# STM32F103UART3.net
KiCad netlist of a schematic drawn in Altium Designer
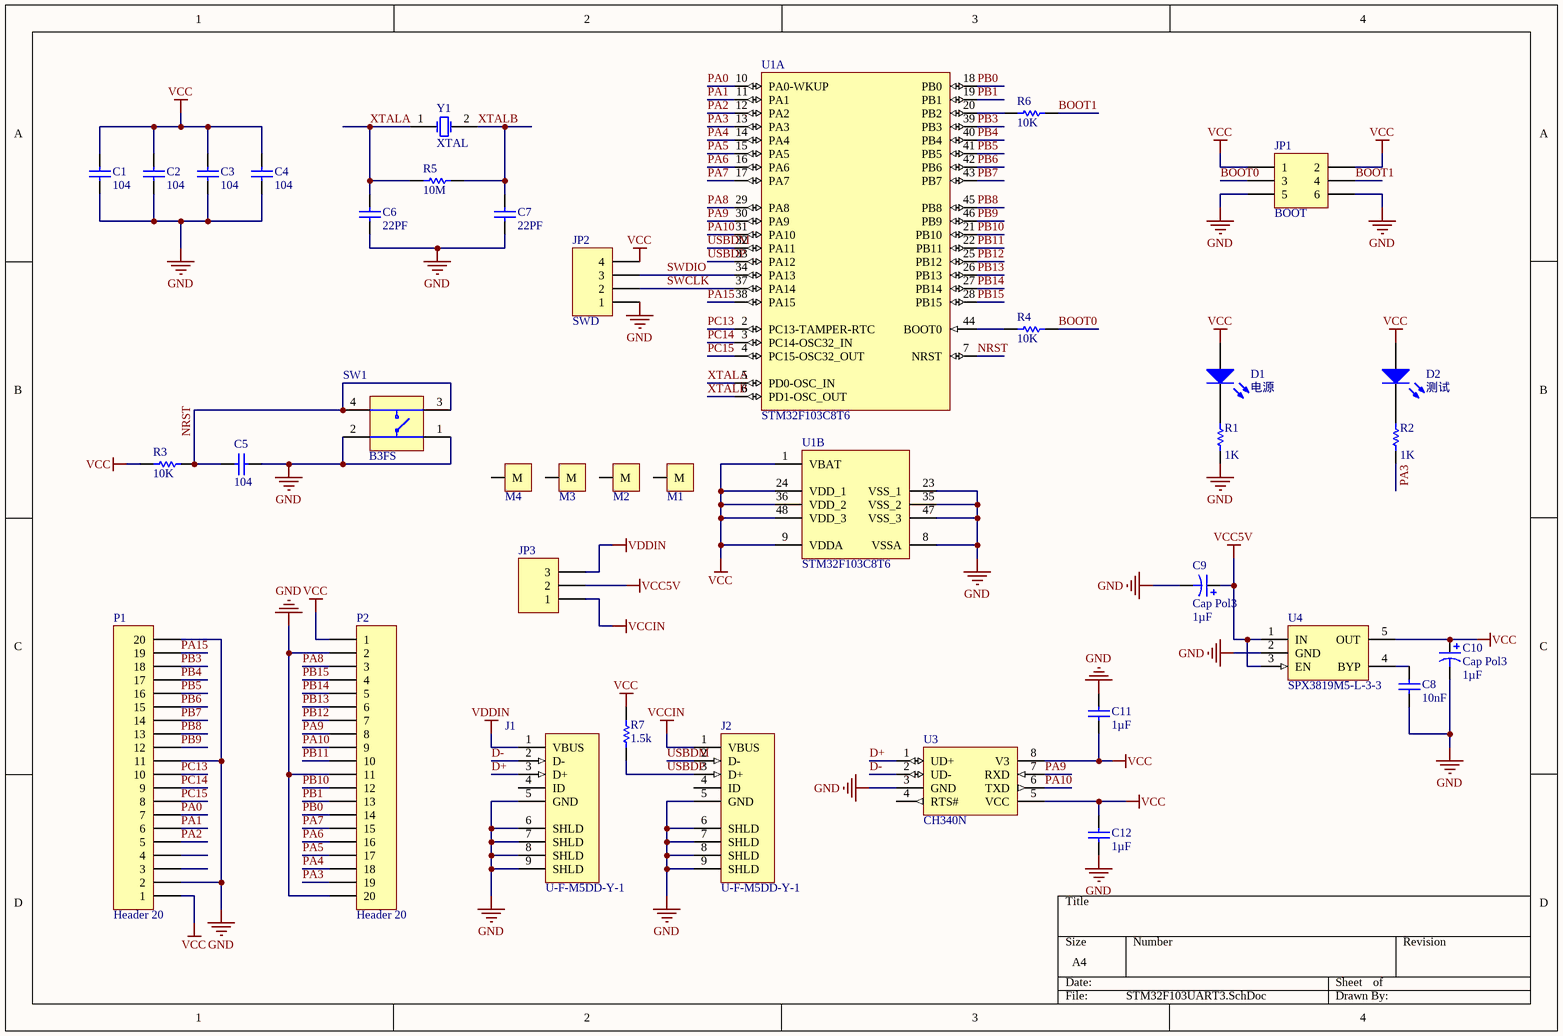
[diagram p0: STM32F103UART3.SchDoc]

(export (version "E")
  (design (tool "Eeschema 10.0.6"))
  (components
    (comp (ref "C1")
      (value "104")
      (footprint "C0603")
      (description "Capacitor (Semiconductor SIM Model)")
      (fields (field (name "Comment") "Cap Semi") (field (name "PUBLISHER") "Altium Limited"))
      (libsource (lib "Miscellaneous Devices") (part "Cap Semi"))
    )
    (comp (ref "C2")
      (value "104")
      (footprint "C0603")
      (description "Capacitor (Semiconductor SIM Model)")
      (fields (field (name "Comment") "Cap Semi") (field (name "PUBLISHER") "Altium Limited"))
      (libsource (lib "Miscellaneous Devices") (part "Cap Semi"))
    )
    (comp (ref "C3")
      (value "104")
      (footprint "C0603")
      (description "Capacitor (Semiconductor SIM Model)")
      (fields (field (name "Comment") "Cap Semi") (field (name "PUBLISHER") "Altium Limited"))
      (libsource (lib "Miscellaneous Devices") (part "Cap Semi"))
    )
    (comp (ref "C4")
      (value "104")
      (footprint "C0603")
      (description "Capacitor (Semiconductor SIM Model)")
      (fields (field (name "Comment") "Cap Semi") (field (name "PUBLISHER") "Altium Limited"))
      (libsource (lib "Miscellaneous Devices") (part "Cap Semi"))
    )
    (comp (ref "C5")
      (value "104")
      (footprint "C0603")
      (description "Capacitor (Semiconductor SIM Model)")
      (fields (field (name "Comment") "Cap Semi") (field (name "PUBLISHER") "Altium Limited"))
      (libsource (lib "Miscellaneous Devices") (part "Cap Semi"))
    )
    (comp (ref "C6")
      (value "22PF")
      (footprint "C0603")
      (description "Capacitor (Semiconductor SIM Model)")
      (fields (field (name "Comment") "Cap Semi") (field (name "PUBLISHER") "Altium Limited"))
      (libsource (lib "Miscellaneous Devices") (part "Cap Semi"))
    )
    (comp (ref "C7")
      (value "22PF")
      (footprint "C0603")
      (description "Capacitor (Semiconductor SIM Model)")
      (fields (field (name "Comment") "Cap Semi") (field (name "PUBLISHER") "Altium Limited"))
      (libsource (lib "Miscellaneous Devices") (part "Cap Semi"))
    )
    (comp (ref "C8")
      (value "10nF")
      (footprint "C0603")
      (description "Capacitor (Semiconductor SIM Model)")
      (fields (field (name "Comment") "Cap Semi") (field (name "PUBLISHER") "Altium Limited"))
      (libsource (lib "Miscellaneous Devices") (part "Cap Semi"))
    )
    (comp (ref "C9")
      (value "Cap Pol3")
      (footprint "C_CASE_A")
      (description "Polarized Capacitor (Surface Mount)")
      (fields (field (name "ALTIUM_VALUE") "1µF") (field (name "PUBLISHER") "Altium Limited"))
      (libsource (lib "Miscellaneous Devices") (part "Cap Pol3"))
    )
    (comp (ref "C10")
      (value "Cap Pol3")
      (footprint "C_CASE_A")
      (description "Polarized Capacitor (Surface Mount)")
      (fields (field (name "ALTIUM_VALUE") "1µF") (field (name "PUBLISHER") "Altium Limited"))
      (libsource (lib "Miscellaneous Devices") (part "Cap Pol3"))
    )
    (comp (ref "C11")
      (value "1µF")
      (footprint "C0603")
      (description "Capacitor (Semiconductor SIM Model)")
      (fields (field (name "Comment") "Cap Semi") (field (name "PUBLISHER") "Altium Limited"))
      (libsource (lib "Miscellaneous Devices") (part "Cap Semi"))
    )
    (comp (ref "C12")
      (value "1µF")
      (footprint "C0603")
      (description "Capacitor (Semiconductor SIM Model)")
      (fields (field (name "Comment") "Cap Semi") (field (name "PUBLISHER") "Altium Limited"))
      (libsource (lib "Miscellaneous Devices") (part "Cap Semi"))
    )
    (comp (ref "D1")
      (value "电源")
      (footprint "LED0603")
      (description "Typical RED, GREEN, YELLOW, AMBER GaAs LED")
      (fields (field (name "PUBLISHER") "Altium Limited"))
      (libsource (lib "Miscellaneous Devices") (part "LED2"))
    )
    (comp (ref "D2")
      (value "测试")
      (footprint "LED0603")
      (description "Typical RED, GREEN, YELLOW, AMBER GaAs LED")
      (fields (field (name "PUBLISHER") "Altium Limited"))
      (libsource (lib "Miscellaneous Devices") (part "LED2"))
    )
    (comp (ref "J1")
      (value "U-F-M5DD-Y-1")
      (footprint "AD14b:USB_MICRO_B_U-F-M5DD-Y-1")
      (description "5-PIN USB SERIES MICRO-B REC")
      (fields (field (name "MANUFACTURER") "HRO") (field (name "PUBLISHER") "Altium Limited"))
      (libsource (lib "AD14b") (part "USB_MICRO"))
    )
    (comp (ref "J2")
      (value "U-F-M5DD-Y-1")
      (footprint "AD14b:USB_MICRO_B_U-F-M5DD-Y-1")
      (description "5-PIN USB SERIES MICRO-B REC")
      (fields (field (name "MANUFACTURER") "HRO") (field (name "PUBLISHER") "Altium Limited"))
      (libsource (lib "AD14b") (part "USB_MICRO"))
    )
    (comp (ref "JP1")
      (value "BOOT")
      (footprint "HDR2X3")
      (description "Header, 3-Pin, Dual row")
      (fields (field (name "PUBLISHER") "Altium Limited"))
      (libsource (lib "Miscellaneous Connectors") (part "Header 3X2"))
    )
    (comp (ref "JP2")
      (value "SWD")
      (footprint "HDR1X4")
      (description "Header, 4-Pin")
      (fields (field (name "PUBLISHER") "Altium Limited"))
      (libsource (lib "Miscellaneous Connectors") (part "Header 4"))
    )
    (comp (ref "JP3")
      (value "Header 3")
      (footprint "HDR1X3")
      (description "Header, 3-Pin")
      (fields (field (name "PUBLISHER") "Altium Limited"))
      (libsource (lib "Miscellaneous Connectors") (part "Header 3"))
    )
    (comp (ref "M1")
      (value "MOUNT")
      (footprint "AD14b:MOUNT3")
      (description "Mount, Hole Size 3mm, Diameter 5.3")
      (fields (field (name "PUBLISHER") "Altium Limited"))
      (libsource (lib "AD14b") (part "MOUNT"))
    )
    (comp (ref "M2")
      (value "MOUNT")
      (footprint "AD14b:MOUNT3")
      (description "Mount, Hole Size 3mm, Diameter 5.3")
      (fields (field (name "PUBLISHER") "Altium Limited"))
      (libsource (lib "AD14b") (part "MOUNT"))
    )
    (comp (ref "M3")
      (value "MOUNT")
      (footprint "AD14b:MOUNT3")
      (description "Mount, Hole Size 3mm, Diameter 5.3")
      (fields (field (name "PUBLISHER") "Altium Limited"))
      (libsource (lib "AD14b") (part "MOUNT"))
    )
    (comp (ref "M4")
      (value "MOUNT")
      (footprint "AD14b:MOUNT3")
      (description "Mount, Hole Size 3mm, Diameter 5.3")
      (fields (field (name "PUBLISHER") "Altium Limited"))
      (libsource (lib "AD14b") (part "MOUNT"))
    )
    (comp (ref "P1")
      (value "Header 20")
      (footprint "HDR1X20")
      (description "Header, 20-Pin")
      (fields (field (name "PUBLISHER") "Altium Limited"))
      (libsource (lib "") (part "Header 20_1"))
    )
    (comp (ref "P2")
      (value "Header 20")
      (footprint "HDR1X20")
      (description "Header, 20-Pin")
      (fields (field (name "PUBLISHER") "Altium Limited"))
      (libsource (lib "Miscellaneous Connectors") (part "Header 20"))
    )
    (comp (ref "R1")
      (value "1K")
      (footprint "R0603")
      (description "Semiconductor Resistor")
      (fields (field (name "Comment") "Res Semi") (field (name "PUBLISHER") "Altium Limited"))
      (libsource (lib "Miscellaneous Devices") (part "Res Semi"))
    )
    (comp (ref "R2")
      (value "1K")
      (footprint "R0603")
      (description "Semiconductor Resistor")
      (fields (field (name "Comment") "Res Semi") (field (name "PUBLISHER") "Altium Limited"))
      (libsource (lib "Miscellaneous Devices") (part "Res Semi"))
    )
    (comp (ref "R3")
      (value "10K")
      (footprint "R0603")
      (description "Semiconductor Resistor")
      (fields (field (name "Comment") "Res Semi") (field (name "PUBLISHER") "Altium Limited"))
      (libsource (lib "Miscellaneous Devices") (part "Res Semi"))
    )
    (comp (ref "R4")
      (value "10K")
      (footprint "R0603")
      (description "Semiconductor Resistor")
      (fields (field (name "Comment") "Res2") (field (name "PUBLISHER") "Altium Limited"))
      (libsource (lib "Miscellaneous Devices") (part "Res Semi"))
    )
    (comp (ref "R5")
      (value "10M")
      (footprint "R0603")
      (description "Semiconductor Resistor")
      (fields (field (name "Comment") "Res3") (field (name "PUBLISHER") "Altium Limited"))
      (libsource (lib "Miscellaneous Devices") (part "Res Semi"))
    )
    (comp (ref "R6")
      (value "10K")
      (footprint "R0603")
      (description "Semiconductor Resistor")
      (fields (field (name "Comment") "Res2") (field (name "PUBLISHER") "Altium Limited"))
      (libsource (lib "Miscellaneous Devices") (part "Res Semi"))
    )
    (comp (ref "R7")
      (value "1.5k")
      (footprint "R0603")
      (description "Semiconductor Resistor")
      (fields (field (name "Comment") "Res3") (field (name "PUBLISHER") "Altium Limited"))
      (libsource (lib "Miscellaneous Devices") (part "Res Semi"))
    )
    (comp (ref "SW1")
      (value "B3FS")
      (footprint "AD14b:SW_B3FS")
      (description "6x6 mm, SPNA SMD Keyboard Switch (TACT Switch)")
      (fields (field (name "PUBLISHER") "Altium Limited"))
      (libsource (lib "AD14b") (part "B3FS"))
    )
    (comp (ref "U1")
      (value "STM32F103C8T6")
      (footprint "STM-LQFP48_N")
      (libsource (lib "STMicroelectronics STM32 F1") (part "STM32F103C8T6"))
    )
    (comp (ref "U3")
      (value "CH340N")
      (footprint "AD14b:SOP8_N")
      (description "USB to Serial Chip")
      (fields (field (name "MANUFACTURER") "WCH") (field (name "PUBLISHER") "Altium Limited"))
      (libsource (lib "AD14b") (part "CH340N"))
    )
    (comp (ref "U4")
      (value "SPX3819M5-L-3-3")
      (footprint "AD14b:SOT-23-5")
      (description "500mA, 16V Low-Noise LDO Voltage Regulator")
      (fields (field (name "MANUFACTURER") "Exar") (field (name "PUBLISHER") "Altium Limited"))
      (libsource (lib "AD14b") (part "SPX3819M5"))
    )
    (comp (ref "Y1")
      (value "XTAL")
      (footprint "OSC5032_2P_AD")
      (description "Crystal Oscillator")
      (fields (field (name "PUBLISHER") "Altium Limited"))
      (libsource (lib "Miscellaneous Devices") (part "XTAL"))
    )
  )
  (nets
    (net (code "1") (name "/BOOT0") (class "Default")
      (node (ref "JP1") (pin "3") (pinfunction "3_3") (pintype "passive"))
      (node (ref "R4") (pin "1") (pinfunction "1_1") (pintype "passive"))
    )
    (net (code "2") (name "/BOOT1") (class "Default")
      (node (ref "JP1") (pin "4") (pinfunction "4_4") (pintype "passive"))
      (node (ref "R6") (pin "1") (pinfunction "1_1") (pintype "passive"))
    )
    (net (code "3") (name "/D+") (class "Default")
      (node (ref "J1") (pin "3") (pinfunction "D+_3") (pintype "input"))
      (node (ref "U3") (pin "1") (pinfunction "UD+_1") (pintype "bidirectional"))
    )
    (net (code "4") (name "/D-") (class "Default")
      (node (ref "J1") (pin "2") (pinfunction "D-_2") (pintype "input"))
      (node (ref "U3") (pin "2") (pinfunction "UD-_2") (pintype "bidirectional"))
    )
    (net (code "5") (name "/NRST") (class "Default")
      (node (ref "C5") (pin "1") (pinfunction "1_1") (pintype "passive"))
      (node (ref "R3") (pin "1") (pinfunction "1_1") (pintype "passive"))
      (node (ref "SW1") (pin "3") (pinfunction "3_3") (pintype "passive"))
      (node (ref "SW1") (pin "4") (pinfunction "4_4") (pintype "passive"))
      (node (ref "U1") (pin "7") (pinfunction "NRST_7") (pintype "bidirectional"))
    )
    (net (code "6") (name "/PA0") (class "Default")
      (node (ref "P1") (pin "7") (pinfunction "7_7") (pintype "passive"))
      (node (ref "U1") (pin "10") (pinfunction "PA0-WKUP_10") (pintype "bidirectional"))
    )
    (net (code "7") (name "/PA1") (class "Default")
      (node (ref "P1") (pin "6") (pinfunction "6_6") (pintype "passive"))
      (node (ref "U1") (pin "11") (pinfunction "PA1_11") (pintype "bidirectional"))
    )
    (net (code "8") (name "/PA2") (class "Default")
      (node (ref "P1") (pin "5") (pinfunction "5_5") (pintype "passive"))
      (node (ref "U1") (pin "12") (pinfunction "PA2_12") (pintype "bidirectional"))
    )
    (net (code "9") (name "/PA3") (class "Default")
      (node (ref "P2") (pin "19") (pinfunction "19_19") (pintype "passive"))
      (node (ref "R2") (pin "1") (pinfunction "1_1") (pintype "passive"))
      (node (ref "U1") (pin "13") (pinfunction "PA3_13") (pintype "bidirectional"))
    )
    (net (code "10") (name "/PA4") (class "Default")
      (node (ref "P2") (pin "18") (pinfunction "18_18") (pintype "passive"))
      (node (ref "U1") (pin "14") (pinfunction "PA4_14") (pintype "bidirectional"))
    )
    (net (code "11") (name "/PA5") (class "Default")
      (node (ref "P2") (pin "17") (pinfunction "17_17") (pintype "passive"))
      (node (ref "U1") (pin "15") (pinfunction "PA5_15") (pintype "bidirectional"))
    )
    (net (code "12") (name "/PA6") (class "Default")
      (node (ref "P2") (pin "16") (pinfunction "16_16") (pintype "passive"))
      (node (ref "U1") (pin "16") (pinfunction "PA6_16") (pintype "bidirectional"))
    )
    (net (code "13") (name "/PA7") (class "Default")
      (node (ref "P2") (pin "15") (pinfunction "15_15") (pintype "passive"))
      (node (ref "U1") (pin "17") (pinfunction "PA7_17") (pintype "bidirectional"))
    )
    (net (code "14") (name "/PA8") (class "Default")
      (node (ref "P2") (pin "3") (pinfunction "3_3") (pintype "passive"))
      (node (ref "U1") (pin "29") (pinfunction "PA8_29") (pintype "bidirectional"))
    )
    (net (code "15") (name "/PA9") (class "Default")
      (node (ref "P2") (pin "8") (pinfunction "8_8") (pintype "passive"))
      (node (ref "U1") (pin "30") (pinfunction "PA9_30") (pintype "bidirectional"))
      (node (ref "U3") (pin "7") (pinfunction "RXD_7") (pintype "input"))
    )
    (net (code "16") (name "/PA10") (class "Default")
      (node (ref "P2") (pin "9") (pinfunction "9_9") (pintype "passive"))
      (node (ref "U1") (pin "31") (pinfunction "PA10_31") (pintype "bidirectional"))
      (node (ref "U3") (pin "6") (pinfunction "TXD_6") (pintype "output"))
    )
    (net (code "17") (name "/PA15") (class "Default")
      (node (ref "P1") (pin "19") (pinfunction "19_19") (pintype "passive"))
      (node (ref "U1") (pin "38") (pinfunction "PA15_38") (pintype "bidirectional"))
    )
    (net (code "18") (name "/PB0") (class "Default")
      (node (ref "P2") (pin "14") (pinfunction "14_14") (pintype "passive"))
      (node (ref "U1") (pin "18") (pinfunction "PB0_18") (pintype "bidirectional"))
    )
    (net (code "19") (name "/PB1") (class "Default")
      (node (ref "P2") (pin "13") (pinfunction "13_13") (pintype "passive"))
      (node (ref "U1") (pin "19") (pinfunction "PB1_19") (pintype "bidirectional"))
    )
    (net (code "20") (name "/PB3") (class "Default")
      (node (ref "P1") (pin "18") (pinfunction "18_18") (pintype "passive"))
      (node (ref "U1") (pin "39") (pinfunction "PB3_39") (pintype "bidirectional"))
    )
    (net (code "21") (name "/PB4") (class "Default")
      (node (ref "P1") (pin "17") (pinfunction "17_17") (pintype "passive"))
      (node (ref "U1") (pin "40") (pinfunction "PB4_40") (pintype "bidirectional"))
    )
    (net (code "22") (name "/PB5") (class "Default")
      (node (ref "P1") (pin "16") (pinfunction "16_16") (pintype "passive"))
      (node (ref "U1") (pin "41") (pinfunction "PB5_41") (pintype "bidirectional"))
    )
    (net (code "23") (name "/PB6") (class "Default")
      (node (ref "P1") (pin "15") (pinfunction "15_15") (pintype "passive"))
      (node (ref "U1") (pin "42") (pinfunction "PB6_42") (pintype "bidirectional"))
    )
    (net (code "24") (name "/PB7") (class "Default")
      (node (ref "P1") (pin "14") (pinfunction "14_14") (pintype "passive"))
      (node (ref "U1") (pin "43") (pinfunction "PB7_43") (pintype "bidirectional"))
    )
    (net (code "25") (name "/PB8") (class "Default")
      (node (ref "P1") (pin "13") (pinfunction "13_13") (pintype "passive"))
      (node (ref "U1") (pin "45") (pinfunction "PB8_45") (pintype "bidirectional"))
    )
    (net (code "26") (name "/PB9") (class "Default")
      (node (ref "P1") (pin "12") (pinfunction "12_12") (pintype "passive"))
      (node (ref "U1") (pin "46") (pinfunction "PB9_46") (pintype "bidirectional"))
    )
    (net (code "27") (name "/PB10") (class "Default")
      (node (ref "P2") (pin "12") (pinfunction "12_12") (pintype "passive"))
      (node (ref "U1") (pin "21") (pinfunction "PB10_21") (pintype "bidirectional"))
    )
    (net (code "28") (name "/PB11") (class "Default")
      (node (ref "P2") (pin "10") (pinfunction "10_10") (pintype "passive"))
      (node (ref "U1") (pin "22") (pinfunction "PB11_22") (pintype "bidirectional"))
    )
    (net (code "29") (name "/PB12") (class "Default")
      (node (ref "P2") (pin "7") (pinfunction "7_7") (pintype "passive"))
      (node (ref "U1") (pin "25") (pinfunction "PB12_25") (pintype "bidirectional"))
    )
    (net (code "30") (name "/PB13") (class "Default")
      (node (ref "P2") (pin "6") (pinfunction "6_6") (pintype "passive"))
      (node (ref "U1") (pin "26") (pinfunction "PB13_26") (pintype "bidirectional"))
    )
    (net (code "31") (name "/PB14") (class "Default")
      (node (ref "P2") (pin "5") (pinfunction "5_5") (pintype "passive"))
      (node (ref "U1") (pin "27") (pinfunction "PB14_27") (pintype "bidirectional"))
    )
    (net (code "32") (name "/PB15") (class "Default")
      (node (ref "P2") (pin "4") (pinfunction "4_4") (pintype "passive"))
      (node (ref "U1") (pin "28") (pinfunction "PB15_28") (pintype "bidirectional"))
    )
    (net (code "33") (name "/PC13") (class "Default")
      (node (ref "P1") (pin "10") (pinfunction "10_10") (pintype "passive"))
      (node (ref "U1") (pin "2") (pinfunction "PC13-TAMPER-RTC_2") (pintype "bidirectional"))
    )
    (net (code "34") (name "/PC14") (class "Default")
      (node (ref "P1") (pin "9") (pinfunction "9_9") (pintype "passive"))
      (node (ref "U1") (pin "3") (pinfunction "PC14-OSC32_IN_3") (pintype "bidirectional"))
    )
    (net (code "35") (name "/PC15") (class "Default")
      (node (ref "P1") (pin "8") (pinfunction "8_8") (pintype "passive"))
      (node (ref "U1") (pin "4") (pinfunction "PC15-OSC32_OUT_4") (pintype "bidirectional"))
    )
    (net (code "36") (name "/SWCLK") (class "Default")
      (node (ref "JP2") (pin "2") (pinfunction "2_2") (pintype "passive"))
      (node (ref "U1") (pin "37") (pinfunction "PA14_37") (pintype "bidirectional"))
    )
    (net (code "37") (name "/SWDIO") (class "Default")
      (node (ref "JP2") (pin "3") (pinfunction "3_3") (pintype "passive"))
      (node (ref "U1") (pin "34") (pinfunction "PA13_34") (pintype "bidirectional"))
    )
    (net (code "38") (name "/USBDM") (class "Default")
      (node (ref "J2") (pin "2") (pinfunction "D-_2") (pintype "input"))
      (node (ref "U1") (pin "32") (pinfunction "PA11_32") (pintype "bidirectional"))
    )
    (net (code "39") (name "/USBDP") (class "Default")
      (node (ref "J2") (pin "3") (pinfunction "D+_3") (pintype "input"))
      (node (ref "R7") (pin "2") (pinfunction "2_2") (pintype "passive"))
      (node (ref "U1") (pin "33") (pinfunction "PA12_33") (pintype "bidirectional"))
    )
    (net (code "40") (name "/XTALA") (class "Default")
      (node (ref "C6") (pin "1") (pinfunction "1_1") (pintype "passive"))
      (node (ref "R5") (pin "2") (pinfunction "2_2") (pintype "passive"))
      (node (ref "U1") (pin "5") (pinfunction "PD0-OSC_IN_5") (pintype "bidirectional"))
      (node (ref "Y1") (pin "1") (pinfunction "OSC1_1") (pintype "passive"))
    )
    (net (code "41") (name "/XTALB") (class "Default")
      (node (ref "C7") (pin "1") (pinfunction "1_1") (pintype "passive"))
      (node (ref "R5") (pin "1") (pinfunction "1_1") (pintype "passive"))
      (node (ref "U1") (pin "6") (pinfunction "PD1-OSC_OUT_6") (pintype "bidirectional"))
      (node (ref "Y1") (pin "2") (pinfunction "OSC2_2") (pintype "passive"))
    )
    (net (code "42") (name "GND") (class "Default")
      (node (ref "C1") (pin "2") (pinfunction "2_2") (pintype "passive"))
      (node (ref "C10") (pin "2") (pinfunction "2_2") (pintype "passive"))
      (node (ref "C11") (pin "2") (pinfunction "2_2") (pintype "passive"))
      (node (ref "C12") (pin "1") (pinfunction "1_1") (pintype "passive"))
      (node (ref "C2") (pin "2") (pinfunction "2_2") (pintype "passive"))
      (node (ref "C3") (pin "2") (pinfunction "2_2") (pintype "passive"))
      (node (ref "C4") (pin "2") (pinfunction "2_2") (pintype "passive"))
      (node (ref "C5") (pin "2") (pinfunction "2_2") (pintype "passive"))
      (node (ref "C6") (pin "2") (pinfunction "2_2") (pintype "passive"))
      (node (ref "C7") (pin "2") (pinfunction "2_2") (pintype "passive"))
      (node (ref "C8") (pin "2") (pinfunction "2_2") (pintype "passive"))
      (node (ref "C9") (pin "2") (pinfunction "2_2") (pintype "passive"))
      (node (ref "J1") (pin "5") (pinfunction "GND_5") (pintype "power_in"))
      (node (ref "J1") (pin "6") (pinfunction "SHLD_6") (pintype "power_in"))
      (node (ref "J1") (pin "7") (pinfunction "SHLD_7") (pintype "power_in"))
      (node (ref "J1") (pin "8") (pinfunction "SHLD_8") (pintype "power_in"))
      (node (ref "J1") (pin "9") (pinfunction "SHLD_9") (pintype "power_in"))
      (node (ref "J2") (pin "5") (pinfunction "GND_5") (pintype "power_in"))
      (node (ref "J2") (pin "6") (pinfunction "SHLD_6") (pintype "power_in"))
      (node (ref "J2") (pin "7") (pinfunction "SHLD_7") (pintype "power_in"))
      (node (ref "J2") (pin "8") (pinfunction "SHLD_8") (pintype "power_in"))
      (node (ref "J2") (pin "9") (pinfunction "SHLD_9") (pintype "power_in"))
      (node (ref "JP1") (pin "5") (pinfunction "5_5") (pintype "passive"))
      (node (ref "JP1") (pin "6") (pinfunction "6_6") (pintype "passive"))
      (node (ref "JP2") (pin "1") (pinfunction "1_1") (pintype "passive"))
      (node (ref "P1") (pin "11") (pinfunction "11_11") (pintype "passive"))
      (node (ref "P1") (pin "2") (pinfunction "2_2") (pintype "passive"))
      (node (ref "P1") (pin "20") (pinfunction "20_20") (pintype "passive"))
      (node (ref "P2") (pin "11") (pinfunction "11_11") (pintype "passive"))
      (node (ref "P2") (pin "2") (pinfunction "2_2") (pintype "passive"))
      (node (ref "P2") (pin "20") (pinfunction "20_20") (pintype "passive"))
      (node (ref "R1") (pin "1") (pinfunction "1_1") (pintype "passive"))
      (node (ref "SW1") (pin "1") (pinfunction "1_1") (pintype "passive"))
      (node (ref "SW1") (pin "2") (pinfunction "2_2") (pintype "passive"))
      (node (ref "U1") (pin "23") (pinfunction "VSS_1_23") (pintype "power_in"))
      (node (ref "U1") (pin "35") (pinfunction "VSS_2_35") (pintype "power_in"))
      (node (ref "U1") (pin "47") (pinfunction "VSS_3_47") (pintype "power_in"))
      (node (ref "U1") (pin "8") (pinfunction "VSSA_8") (pintype "power_in"))
      (node (ref "U3") (pin "3") (pinfunction "GND_3") (pintype "power_in"))
      (node (ref "U4") (pin "2") (pinfunction "GND_2") (pintype "power_in"))
    )
    (net (code "43") (name "Net-(D1-K)") (class "Default")
      (node (ref "D1") (pin "2") (pinfunction "K_2") (pintype "passive"))
      (node (ref "R1") (pin "2") (pinfunction "2_2") (pintype "passive"))
    )
    (net (code "44") (name "Net-(D2-K)") (class "Default")
      (node (ref "D2") (pin "2") (pinfunction "K_2") (pintype "passive"))
      (node (ref "R2") (pin "2") (pinfunction "2_2") (pintype "passive"))
    )
    (net (code "45") (name "Net-(U1A-BOOT0)") (class "Default")
      (node (ref "R4") (pin "2") (pinfunction "2_2") (pintype "passive"))
      (node (ref "U1") (pin "44") (pinfunction "BOOT0_44") (pintype "input"))
    )
    (net (code "46") (name "Net-(U1A-PB2)") (class "Default")
      (node (ref "R6") (pin "2") (pinfunction "2_2") (pintype "passive"))
      (node (ref "U1") (pin "20") (pinfunction "PB2_20") (pintype "bidirectional"))
    )
    (net (code "47") (name "Net-(U4-BYP)") (class "Default")
      (node (ref "C8") (pin "1") (pinfunction "1_1") (pintype "passive"))
      (node (ref "U4") (pin "4") (pinfunction "BYP_4") (pintype "passive"))
    )
    (net (code "48") (name "VCC") (class "Default")
      (node (ref "C1") (pin "1") (pinfunction "1_1") (pintype "passive"))
      (node (ref "C10") (pin "1") (pinfunction "1_1") (pintype "passive"))
      (node (ref "C11") (pin "1") (pinfunction "1_1") (pintype "passive"))
      (node (ref "C12") (pin "2") (pinfunction "2_2") (pintype "passive"))
      (node (ref "C2") (pin "1") (pinfunction "1_1") (pintype "passive"))
      (node (ref "C3") (pin "1") (pinfunction "1_1") (pintype "passive"))
      (node (ref "C4") (pin "1") (pinfunction "1_1") (pintype "passive"))
      (node (ref "D1") (pin "1") (pinfunction "A_1") (pintype "passive"))
      (node (ref "D2") (pin "1") (pinfunction "A_1") (pintype "passive"))
      (node (ref "JP1") (pin "1") (pinfunction "1_1") (pintype "passive"))
      (node (ref "JP1") (pin "2") (pinfunction "2_2") (pintype "passive"))
      (node (ref "JP2") (pin "4") (pinfunction "4_4") (pintype "passive"))
      (node (ref "P1") (pin "1") (pinfunction "1_1") (pintype "passive"))
      (node (ref "P2") (pin "1") (pinfunction "1_1") (pintype "passive"))
      (node (ref "R3") (pin "2") (pinfunction "2_2") (pintype "passive"))
      (node (ref "R7") (pin "1") (pinfunction "1_1") (pintype "passive"))
      (node (ref "U1") (pin "1") (pinfunction "VBAT_1") (pintype "power_in"))
      (node (ref "U1") (pin "24") (pinfunction "VDD_1_24") (pintype "power_in"))
      (node (ref "U1") (pin "36") (pinfunction "VDD_2_36") (pintype "power_in"))
      (node (ref "U1") (pin "48") (pinfunction "VDD_3_48") (pintype "power_in"))
      (node (ref "U1") (pin "9") (pinfunction "VDDA_9") (pintype "power_in"))
      (node (ref "U3") (pin "5") (pinfunction "VCC_5") (pintype "power_in"))
      (node (ref "U3") (pin "8") (pinfunction "V3_8") (pintype "power_in"))
      (node (ref "U4") (pin "5") (pinfunction "OUT_5") (pintype "power_in"))
    )
    (net (code "49") (name "VCC5V") (class "Default")
      (node (ref "C9") (pin "1") (pinfunction "1_1") (pintype "passive"))
      (node (ref "JP3") (pin "2") (pinfunction "2_2") (pintype "passive"))
      (node (ref "U4") (pin "1") (pinfunction "IN_1") (pintype "power_in"))
      (node (ref "U4") (pin "3") (pinfunction "EN_3") (pintype "input"))
    )
    (net (code "50") (name "VCCIN") (class "Default")
      (node (ref "J2") (pin "1") (pinfunction "VBUS_1") (pintype "power_in"))
      (node (ref "JP3") (pin "1") (pinfunction "1_1") (pintype "passive"))
    )
    (net (code "51") (name "VDDIN") (class "Default")
      (node (ref "J1") (pin "1") (pinfunction "VBUS_1") (pintype "power_in"))
      (node (ref "JP3") (pin "3") (pinfunction "3_3") (pintype "passive"))
    )
    (net (code "52") (name "unconnected-(J1-ID-Pad4)") (class "Default")
      (node (ref "J1") (pin "4") (pinfunction "ID_4") (pintype "passive"))
    )
    (net (code "53") (name "unconnected-(J2-ID-Pad4)") (class "Default")
      (node (ref "J2") (pin "4") (pinfunction "ID_4") (pintype "passive"))
    )
    (net (code "54") (name "unconnected-(M1-M-Pad1)") (class "Default")
      (node (ref "M1") (pin "1") (pinfunction "M_1") (pintype "passive"))
    )
    (net (code "55") (name "unconnected-(M2-M-Pad1)") (class "Default")
      (node (ref "M2") (pin "1") (pinfunction "M_1") (pintype "passive"))
    )
    (net (code "56") (name "unconnected-(M3-M-Pad1)") (class "Default")
      (node (ref "M3") (pin "1") (pinfunction "M_1") (pintype "passive"))
    )
    (net (code "57") (name "unconnected-(M4-M-Pad1)") (class "Default")
      (node (ref "M4") (pin "1") (pinfunction "M_1") (pintype "passive"))
    )
    (net (code "58") (name "unconnected-(P1-Pad3)") (class "Default")
      (node (ref "P1") (pin "3") (pinfunction "3_3") (pintype "passive"))
    )
    (net (code "59") (name "unconnected-(P1-Pad4)") (class "Default")
      (node (ref "P1") (pin "4") (pinfunction "4_4") (pintype "passive"))
    )
    (net (code "60") (name "unconnected-(U3-RTS#-Pad4)") (class "Default")
      (node (ref "U3") (pin "4") (pinfunction "RTS#_4") (pintype "output"))
    )
  )
)
